# MCU.net
KiCad netlist of a schematic drawn in Altium Designer
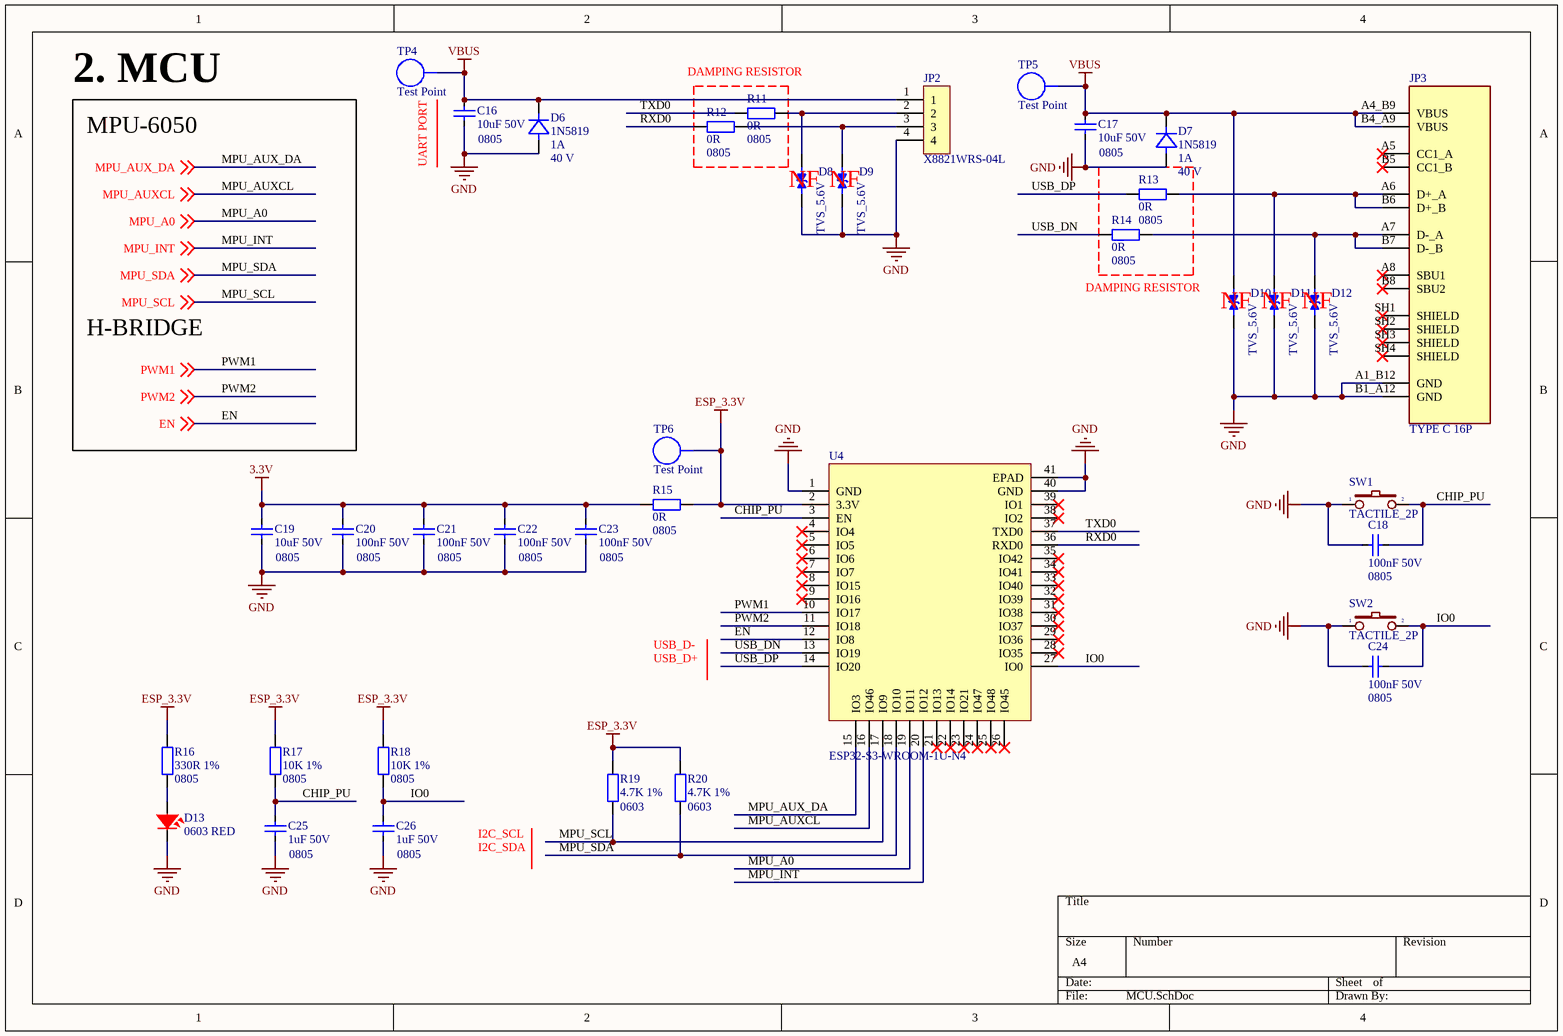
[diagram p0: MCU.SchDoc]

(export (version "E")
  (design (tool "Eeschema 10.0.6"))
  (components
    (comp (ref "C16")
      (value "10uF 50V")
      (footprint "CAP_SMD_0805_NEW")
      (description "10 µF ±20% 50V Ceramic Capacitor X5R 0805 (2012 Metric)")
      (fields
        (field (name "MANUFACTURER") "Murata Electronics")
        (field (name "MANUFACTURE PART NUMBER") "GRM21BR61H106ME43L")
        (field (name "SIZE") "0805")
      )
      (libsource (lib "Capacitors") (part "C0805_MLCC_10uF_50V"))
    )
    (comp (ref "C17")
      (value "10uF 50V")
      (footprint "CAP_SMD_0805_NEW")
      (description "10 µF ±20% 50V Ceramic Capacitor X5R 0805 (2012 Metric)")
      (fields
        (field (name "MANUFACTURER") "Murata Electronics")
        (field (name "MANUFACTURE PART NUMBER") "GRM21BR61H106ME43L")
        (field (name "SIZE") "0805")
      )
      (libsource (lib "Capacitors") (part "C0805_MLCC_10uF_50V"))
    )
    (comp (ref "C18")
      (value "100nF 50V")
      (footprint "CAP_SMD_0805_NEW")
      (description "0.1 µF ±10% 50V Ceramic Capacitor X7R 0805 (2012 Metric)")
      (fields
        (field (name "MANUFACTURER") "YAGEO")
        (field (name "MANUFACTURE PART NUMBER") "CC0805KRX7R9BB104")
        (field (name "SIZE") "0805")
      )
      (libsource (lib "Capacitors") (part "C0805_MLCC_100nF_50V"))
    )
    (comp (ref "C19")
      (value "10uF 50V")
      (footprint "CAP_SMD_0805_NEW")
      (description "10 µF ±20% 50V Ceramic Capacitor X5R 0805 (2012 Metric)")
      (fields
        (field (name "MANUFACTURER") "Murata Electronics")
        (field (name "MANUFACTURE PART NUMBER") "GRM21BR61H106ME43L")
        (field (name "SIZE") "0805")
      )
      (libsource (lib "Capacitors") (part "C0805_MLCC_10uF_50V"))
    )
    (comp (ref "C20")
      (value "100nF 50V")
      (footprint "CAP_SMD_0805_NEW")
      (description "0.1 µF ±10% 50V Ceramic Capacitor X7R 0805 (2012 Metric)")
      (fields
        (field (name "MANUFACTURER") "YAGEO")
        (field (name "MANUFACTURE PART NUMBER") "CC0805KRX7R9BB104")
        (field (name "SIZE") "0805")
      )
      (libsource (lib "Capacitors") (part "C0805_MLCC_100nF_50V"))
    )
    (comp (ref "C21")
      (value "100nF 50V")
      (footprint "CAP_SMD_0805_NEW")
      (description "0.1 µF ±10% 50V Ceramic Capacitor X7R 0805 (2012 Metric)")
      (fields
        (field (name "MANUFACTURER") "YAGEO")
        (field (name "MANUFACTURE PART NUMBER") "CC0805KRX7R9BB104")
        (field (name "SIZE") "0805")
      )
      (libsource (lib "Capacitors") (part "C0805_MLCC_100nF_50V"))
    )
    (comp (ref "C22")
      (value "100nF 50V")
      (footprint "CAP_SMD_0805_NEW")
      (description "0.1 µF ±10% 50V Ceramic Capacitor X7R 0805 (2012 Metric)")
      (fields
        (field (name "MANUFACTURER") "YAGEO")
        (field (name "MANUFACTURE PART NUMBER") "CC0805KRX7R9BB104")
        (field (name "SIZE") "0805")
      )
      (libsource (lib "Capacitors") (part "C0805_MLCC_100nF_50V"))
    )
    (comp (ref "C23")
      (value "100nF 50V")
      (footprint "CAP_SMD_0805_NEW")
      (description "0.1 µF ±10% 50V Ceramic Capacitor X7R 0805 (2012 Metric)")
      (fields
        (field (name "MANUFACTURER") "YAGEO")
        (field (name "MANUFACTURE PART NUMBER") "CC0805KRX7R9BB104")
        (field (name "SIZE") "0805")
      )
      (libsource (lib "Capacitors") (part "C0805_MLCC_100nF_50V"))
    )
    (comp (ref "C24")
      (value "100nF 50V")
      (footprint "CAP_SMD_0805_NEW")
      (description "0.1 µF ±10% 50V Ceramic Capacitor X7R 0805 (2012 Metric)")
      (fields
        (field (name "MANUFACTURER") "YAGEO")
        (field (name "MANUFACTURE PART NUMBER") "CC0805KRX7R9BB104")
        (field (name "SIZE") "0805")
      )
      (libsource (lib "Capacitors") (part "C0805_MLCC_100nF_50V"))
    )
    (comp (ref "C25")
      (value "1uF 50V")
      (footprint "CAP_SMD_0805_NEW")
      (description "1 µF ±10% 50V Ceramic Capacitor X7R 0805 (2012 Metric)")
      (fields
        (field (name "MANUFACTURER") "Samsung Electro-Mechanics")
        (field (name "MANUFACTURE PART NUMBER") "CL21B105KBFNNNG")
        (field (name "SIZE") "0805")
      )
      (libsource (lib "Capacitors") (part "C0805_MLCC_1uF_50V"))
    )
    (comp (ref "C26")
      (value "1uF 50V")
      (footprint "CAP_SMD_0805_NEW")
      (description "1 µF ±10% 50V Ceramic Capacitor X7R 0805 (2012 Metric)")
      (fields
        (field (name "MANUFACTURER") "Samsung Electro-Mechanics")
        (field (name "MANUFACTURE PART NUMBER") "CL21B105KBFNNNG")
        (field (name "SIZE") "0805")
      )
      (libsource (lib "Capacitors") (part "C0805_MLCC_1uF_50V"))
    )
    (comp (ref "D6")
      (value "1N5819")
      (footprint "DIO-SMD-123")
      (description "Diode 40 V 1A Surface Mount SOD-123")
      (fields
        (field (name "MANUFACTURER") "Diodes Incorporated")
        (field (name "MANUFACTURE PART NUMBER") "1N5819HW-7-F")
        (field (name "CURRENT - AVERAGE RECTIFIED (IO)") "1A")
        (field (name "VOLTAGE - DC REVERSE (VR) (MAX)") "40 V")
      )
      (libsource (lib "Diode") (part "1N5819"))
    )
    (comp (ref "D7")
      (value "1N5819")
      (footprint "DIO-SMD-123")
      (description "Diode 40 V 1A Surface Mount SOD-123")
      (fields
        (field (name "MANUFACTURER") "Diodes Incorporated")
        (field (name "MANUFACTURE PART NUMBER") "1N5819HW-7-F")
        (field (name "CURRENT - AVERAGE RECTIFIED (IO)") "1A")
        (field (name "VOLTAGE - DC REVERSE (VR) (MAX)") "40 V")
      )
      (libsource (lib "Diode") (part "1N5819"))
    )
    (comp (ref "D8")
      (value "TVS_5.6V")
      (footprint "SOD_523")
      (description "9.4A 18.6V 5.6V Bi-Directional 5V SOD-523 Electrostatic and Surge Protection (TVS/ESD) ROHS")
      (fields (field (name "MANUFACTURER") "LRC") (field (name "MANUFACTURE PART NUMBER") "LESD5D5.0CT1G"))
      (libsource (lib "Diode") (part "TVS_5.6V"))
    )
    (comp (ref "D9")
      (value "TVS_5.6V")
      (footprint "SOD_523")
      (description "9.4A 18.6V 5.6V Bi-Directional 5V SOD-523 Electrostatic and Surge Protection (TVS/ESD) ROHS")
      (fields (field (name "MANUFACTURER") "LRC") (field (name "MANUFACTURE PART NUMBER") "LESD5D5.0CT1G"))
      (libsource (lib "Diode") (part "TVS_5.6V"))
    )
    (comp (ref "D10")
      (value "TVS_5.6V")
      (footprint "SOD_523")
      (description "9.4A 18.6V 5.6V Bi-Directional 5V SOD-523 Electrostatic and Surge Protection (TVS/ESD) ROHS")
      (fields (field (name "MANUFACTURER") "LRC") (field (name "MANUFACTURE PART NUMBER") "LESD5D5.0CT1G"))
      (libsource (lib "Diode") (part "TVS_5.6V"))
    )
    (comp (ref "D11")
      (value "TVS_5.6V")
      (footprint "SOD_523")
      (description "9.4A 18.6V 5.6V Bi-Directional 5V SOD-523 Electrostatic and Surge Protection (TVS/ESD) ROHS")
      (fields (field (name "MANUFACTURER") "LRC") (field (name "MANUFACTURE PART NUMBER") "LESD5D5.0CT1G"))
      (libsource (lib "Diode") (part "TVS_5.6V"))
    )
    (comp (ref "D12")
      (value "TVS_5.6V")
      (footprint "SOD_523")
      (description "9.4A 18.6V 5.6V Bi-Directional 5V SOD-523 Electrostatic and Surge Protection (TVS/ESD) ROHS")
      (fields (field (name "MANUFACTURER") "LRC") (field (name "MANUFACTURE PART NUMBER") "LESD5D5.0CT1G"))
      (libsource (lib "Diode") (part "TVS_5.6V"))
    )
    (comp (ref "D13")
      (value "0603 RED")
      (footprint "LED-0603")
      (description "Red 625nm LED Indication - Discrete 2V 0603 (1608 Metric)")
      (fields
        (field (name "MANUFACTURER") "Würth Elektronik")
        (field (name "MANUFACTURE PART NUMBER") "150060RS75000")
      )
      (libsource (lib "LEDs") (part "LED_0603_RED"))
    )
    (comp (ref "JP2")
      (value "X8821WRS-04L")
      (footprint "CONN_X8821WRS-04L-LPSN")
      (fields
        (field (name "MANUFACTURER") "XKB Connection")
        (field (name "MANUFACTURE PART NUMBER") "X8821WRS-04-9TSN")
      )
      (libsource (lib "Connectors") (part "X8821WRS-04L"))
    )
    (comp (ref "JP3")
      (value "TYPE C 16P")
      (footprint "TYPE C 16P")
      (fields
        (field (name "MANUFACTURER") "Amphenol ICC (Commercial Products)")
        (field (name "MANUFACTURE PART NUMBER") "12402012E212A")
      )
      (libsource (lib "Connectors") (part "TYPE_C_16P"))
    )
    (comp (ref "R11")
      (value "0R")
      (footprint "RES_SMD_0805")
      (description "0 Ohms Jumper Chip Resistor 0805 (2012 Metric) Automotive AEC-Q200 Thick Film")
      (fields
        (field (name "MANUFACTURER") "Vishay Dale")
        (field (name "MANUFACTURE PART NUMBER") "CRCW08050000Z0EA")
        (field (name "SIZE") "0805")
      )
      (libsource (lib "Resistors") (part "R0805_0R"))
    )
    (comp (ref "R12")
      (value "0R")
      (footprint "RES_SMD_0805")
      (description "0 Ohms Jumper Chip Resistor 0805 (2012 Metric) Automotive AEC-Q200 Thick Film")
      (fields
        (field (name "MANUFACTURER") "Vishay Dale")
        (field (name "MANUFACTURE PART NUMBER") "CRCW08050000Z0EA")
        (field (name "SIZE") "0805")
      )
      (libsource (lib "Resistors") (part "R0805_0R"))
    )
    (comp (ref "R13")
      (value "0R")
      (footprint "RES_SMD_0805")
      (description "0 Ohms Jumper Chip Resistor 0805 (2012 Metric) Automotive AEC-Q200 Thick Film")
      (fields
        (field (name "MANUFACTURER") "Vishay Dale")
        (field (name "MANUFACTURE PART NUMBER") "CRCW08050000Z0EA")
        (field (name "SIZE") "0805")
      )
      (libsource (lib "Resistors") (part "R0805_0R"))
    )
    (comp (ref "R14")
      (value "0R")
      (footprint "RES_SMD_0805")
      (description "0 Ohms Jumper Chip Resistor 0805 (2012 Metric) Automotive AEC-Q200 Thick Film")
      (fields
        (field (name "MANUFACTURER") "Vishay Dale")
        (field (name "MANUFACTURE PART NUMBER") "CRCW08050000Z0EA")
        (field (name "SIZE") "0805")
      )
      (libsource (lib "Resistors") (part "R0805_0R"))
    )
    (comp (ref "R15")
      (value "0R")
      (footprint "RES_SMD_0805")
      (description "0 Ohms Jumper Chip Resistor 0805 (2012 Metric) Automotive AEC-Q200 Thick Film")
      (fields
        (field (name "MANUFACTURER") "Vishay Dale")
        (field (name "MANUFACTURE PART NUMBER") "CRCW08050000Z0EA")
        (field (name "SIZE") "0805")
      )
      (libsource (lib "Resistors") (part "R0805_0R"))
    )
    (comp (ref "R16")
      (value "330R 1%")
      (footprint "RES_SMD_0805")
      (description "330 Ohms ±1% 0.125W, 1/8W Chip Resistor 0805 (2012 Metric) Automotive AEC-Q200 Thick Film")
      (fields
        (field (name "MANUFACTURER") "Stackpole Electronics Inc")
        (field (name "MANUFACTURE PART NUMBER") "RMCF0805FT330R")
        (field (name "SIZE") "0805")
      )
      (libsource (lib "Resistors") (part "R0805_330R"))
    )
    (comp (ref "R17")
      (value "10K 1%")
      (footprint "RES_SMD_0805")
      (description "10 kOhms ±1% 0.125W, 1/8W Chip Resistor 0805 (2012 Metric) Moisture Resistant Thick Film")
      (fields
        (field (name "MANUFACTURER") "YAGEO")
        (field (name "MANUFACTURE PART NUMBER") "RC0805FR-0710KL")
        (field (name "SIZE") "0805")
      )
      (libsource (lib "Resistors") (part "R0805_10K"))
    )
    (comp (ref "R18")
      (value "10K 1%")
      (footprint "RES_SMD_0805")
      (description "10 kOhms ±1% 0.125W, 1/8W Chip Resistor 0805 (2012 Metric) Moisture Resistant Thick Film")
      (fields
        (field (name "MANUFACTURER") "YAGEO")
        (field (name "MANUFACTURE PART NUMBER") "RC0805FR-0710KL")
        (field (name "SIZE") "0805")
      )
      (libsource (lib "Resistors") (part "R0805_10K"))
    )
    (comp (ref "R19")
      (value "4.7K 1%")
      (footprint "RES_SMD_0603")
      (description "4.7 kOhms ±1% 0.1W, 1/10W Chip Resistor 0603 (1608 Metric) Moisture Resistant Thick Film")
      (fields
        (field (name "MANUFACTURER") "YAGEO")
        (field (name "MANUFACTURE PART NUMBER") "RC0603FR-074K7L")
        (field (name "SIZE") "0603")
      )
      (libsource (lib "Resistors") (part "R0603_4.7K"))
    )
    (comp (ref "R20")
      (value "4.7K 1%")
      (footprint "RES_SMD_0603")
      (description "4.7 kOhms ±1% 0.1W, 1/10W Chip Resistor 0603 (1608 Metric) Moisture Resistant Thick Film")
      (fields
        (field (name "MANUFACTURER") "YAGEO")
        (field (name "MANUFACTURE PART NUMBER") "RC0603FR-074K7L")
        (field (name "SIZE") "0603")
      )
      (libsource (lib "Resistors") (part "R0603_4.7K"))
    )
    (comp (ref "SW1")
      (value "TACTILE_2P")
      (footprint "C&K SW 2P")
      (description "Tactile Switch SPST-NO Top Actuated Surface Mount")
      (fields
        (field (name "MANUFACTURER") "C&K")
        (field (name "MANUFACTURE PART NUMBER") "PTS636 SM25F SMTR LFS")
      )
      (libsource (lib "Button") (part "SWITCH_TACTILE_SPST"))
    )
    (comp (ref "SW2")
      (value "TACTILE_2P")
      (footprint "C&K SW 2P")
      (description "Tactile Switch SPST-NO Top Actuated Surface Mount")
      (fields
        (field (name "MANUFACTURER") "C&K")
        (field (name "MANUFACTURE PART NUMBER") "PTS636 SM25F SMTR LFS")
      )
      (libsource (lib "Button") (part "SWITCH_TACTILE_SPST"))
    )
    (comp (ref "TP4")
      (value "Test Point")
      (footprint "TEST_POINT")
      (libsource (lib "Connectors") (part "TEST_POINT"))
    )
    (comp (ref "TP5")
      (value "Test Point")
      (footprint "TEST_POINT")
      (libsource (lib "Connectors") (part "TEST_POINT"))
    )
    (comp (ref "TP6")
      (value "Test Point")
      (footprint "TEST_POINT")
      (libsource (lib "Connectors") (part "TEST_POINT"))
    )
    (comp (ref "U4")
      (value "ESP32-S3-WROOM-1U-N4")
      (footprint "ESP32-S3-WROOM-1U")
      (description "SMD,18x19.2mm WiFi Modules ROHS")
      (fields (field (name "MANUFACTURER") "Espressif Systems"))
      (libsource (lib "MCU") (part "ESP32-S3-WROOM-1U-N4"))
    )
  )
  (nets
    (net (code "1") (name "/CHIP_PU") (class "Default")
      (node (ref "C18") (pin "1") (pinfunction "1_1") (pintype "passive"))
      (node (ref "C25") (pin "2") (pinfunction "2_2") (pintype "passive"))
      (node (ref "R17") (pin "1") (pinfunction "1_1") (pintype "passive"))
      (node (ref "SW1") (pin "2") (pinfunction "2_2") (pintype "passive"))
      (node (ref "U4") (pin "3") (pinfunction "EN_3") (pintype "passive"))
    )
    (net (code "2") (name "/IO0") (class "Default")
      (node (ref "C24") (pin "1") (pinfunction "1_1") (pintype "passive"))
      (node (ref "C26") (pin "2") (pinfunction "2_2") (pintype "passive"))
      (node (ref "R18") (pin "1") (pinfunction "1_1") (pintype "passive"))
      (node (ref "SW2") (pin "2") (pinfunction "2_2") (pintype "passive"))
      (node (ref "U4") (pin "27") (pinfunction "IO0_27") (pintype "passive"))
    )
    (net (code "3") (name "/RXD0") (class "Default")
      (node (ref "R12") (pin "2") (pinfunction "2_2") (pintype "passive"))
      (node (ref "U4") (pin "36") (pinfunction "RXD0_36") (pintype "passive"))
    )
    (net (code "4") (name "/TXD0") (class "Default")
      (node (ref "R11") (pin "2") (pinfunction "2_2") (pintype "passive"))
      (node (ref "U4") (pin "37") (pinfunction "TXD0_37") (pintype "passive"))
    )
    (net (code "5") (name "/USB_DN") (class "Default")
      (node (ref "R14") (pin "2") (pinfunction "2_2") (pintype "passive"))
      (node (ref "U4") (pin "13") (pinfunction "IO19_13") (pintype "passive"))
    )
    (net (code "6") (name "/USB_DP") (class "Default")
      (node (ref "R13") (pin "2") (pinfunction "2_2") (pintype "passive"))
      (node (ref "U4") (pin "14") (pinfunction "IO20_14") (pintype "passive"))
    )
    (net (code "7") (name "3.3V") (class "Default")
      (node (ref "C19") (pin "2") (pinfunction "2_2") (pintype "passive"))
      (node (ref "C20") (pin "2") (pinfunction "2_2") (pintype "passive"))
      (node (ref "C21") (pin "2") (pinfunction "2_2") (pintype "passive"))
      (node (ref "C22") (pin "2") (pinfunction "2_2") (pintype "passive"))
      (node (ref "C23") (pin "2") (pinfunction "2_2") (pintype "passive"))
      (node (ref "R15") (pin "2") (pinfunction "2_2") (pintype "passive"))
    )
    (net (code "8") (name "EN") (class "Default")
      (node (ref "U4") (pin "12") (pinfunction "IO8_12") (pintype "passive"))
    )
    (net (code "9") (name "ESP_3.3V") (class "Default")
      (node (ref "R15") (pin "1") (pinfunction "1_1") (pintype "passive"))
      (node (ref "R16") (pin "2") (pinfunction "2_2") (pintype "passive"))
      (node (ref "R17") (pin "2") (pinfunction "2_2") (pintype "passive"))
      (node (ref "R18") (pin "2") (pinfunction "2_2") (pintype "passive"))
      (node (ref "R19") (pin "2") (pinfunction "2_2") (pintype "passive"))
      (node (ref "R20") (pin "2") (pinfunction "2_2") (pintype "passive"))
      (node (ref "TP6") (pin "1") (pinfunction "1_1") (pintype "passive"))
      (node (ref "U4") (pin "2") (pinfunction "3.3V_2") (pintype "passive"))
    )
    (net (code "10") (name "GND") (class "Default")
      (node (ref "C16") (pin "1") (pinfunction "1_1") (pintype "passive"))
      (node (ref "C17") (pin "1") (pinfunction "1_1") (pintype "passive"))
      (node (ref "C18") (pin "2") (pinfunction "2_2") (pintype "passive"))
      (node (ref "C19") (pin "1") (pinfunction "1_1") (pintype "passive"))
      (node (ref "C20") (pin "1") (pinfunction "1_1") (pintype "passive"))
      (node (ref "C21") (pin "1") (pinfunction "1_1") (pintype "passive"))
      (node (ref "C22") (pin "1") (pinfunction "1_1") (pintype "passive"))
      (node (ref "C23") (pin "1") (pinfunction "1_1") (pintype "passive"))
      (node (ref "C24") (pin "2") (pinfunction "2_2") (pintype "passive"))
      (node (ref "C25") (pin "1") (pinfunction "1_1") (pintype "passive"))
      (node (ref "C26") (pin "1") (pinfunction "1_1") (pintype "passive"))
      (node (ref "D10") (pin "1") (pinfunction "1_1") (pintype "passive"))
      (node (ref "D11") (pin "1") (pinfunction "1_1") (pintype "passive"))
      (node (ref "D12") (pin "1") (pinfunction "1_1") (pintype "passive"))
      (node (ref "D13") (pin "2") (pinfunction "2_2") (pintype "passive"))
      (node (ref "D6") (pin "A") (pinfunction "A_A") (pintype "passive"))
      (node (ref "D7") (pin "A") (pinfunction "A_A") (pintype "passive"))
      (node (ref "D8") (pin "1") (pinfunction "1_1") (pintype "passive"))
      (node (ref "D9") (pin "1") (pinfunction "1_1") (pintype "passive"))
      (node (ref "JP2") (pin "4") (pinfunction "4_4") (pintype "passive"))
      (node (ref "JP3") (pin "A1_B12") (pinfunction "GND_A1_B12") (pintype "passive"))
      (node (ref "JP3") (pin "B1_A12") (pinfunction "GND_B1_A12") (pintype "passive"))
      (node (ref "SW1") (pin "1") (pinfunction "1_1") (pintype "passive"))
      (node (ref "SW2") (pin "1") (pinfunction "1_1") (pintype "passive"))
      (node (ref "U4") (pin "1") (pinfunction "GND_1") (pintype "passive"))
      (node (ref "U4") (pin "40") (pinfunction "GND_40") (pintype "passive"))
      (node (ref "U4") (pin "41") (pinfunction "EPAD_41") (pintype "passive"))
    )
    (net (code "11") (name "MPU_A0") (class "Default")
      (node (ref "U4") (pin "19") (pinfunction "IO11_19") (pintype "passive"))
    )
    (net (code "12") (name "MPU_AUXCL") (class "Default")
      (node (ref "U4") (pin "16") (pinfunction "IO46_16") (pintype "passive"))
    )
    (net (code "13") (name "MPU_AUX_DA") (class "Default")
      (node (ref "U4") (pin "15") (pinfunction "IO3_15") (pintype "passive"))
    )
    (net (code "14") (name "MPU_INT") (class "Default")
      (node (ref "U4") (pin "20") (pinfunction "IO12_20") (pintype "passive"))
    )
    (net (code "15") (name "MPU_SCL") (class "Default")
      (node (ref "R19") (pin "1") (pinfunction "1_1") (pintype "passive"))
      (node (ref "U4") (pin "17") (pinfunction "IO9_17") (pintype "passive"))
    )
    (net (code "16") (name "MPU_SDA") (class "Default")
      (node (ref "R20") (pin "1") (pinfunction "1_1") (pintype "passive"))
      (node (ref "U4") (pin "18") (pinfunction "IO10_18") (pintype "passive"))
    )
    (net (code "17") (name "Net-(D8-Pad2)") (class "Default")
      (node (ref "D8") (pin "2") (pinfunction "2_2") (pintype "passive"))
      (node (ref "JP2") (pin "2") (pinfunction "2_2") (pintype "passive"))
      (node (ref "R11") (pin "1") (pinfunction "1_1") (pintype "passive"))
    )
    (net (code "18") (name "Net-(D9-Pad2)") (class "Default")
      (node (ref "D9") (pin "2") (pinfunction "2_2") (pintype "passive"))
      (node (ref "JP2") (pin "3") (pinfunction "3_3") (pintype "passive"))
      (node (ref "R12") (pin "1") (pinfunction "1_1") (pintype "passive"))
    )
    (net (code "19") (name "Net-(D13-Pad1)") (class "Default")
      (node (ref "D13") (pin "1") (pinfunction "1_1") (pintype "passive"))
      (node (ref "R16") (pin "1") (pinfunction "1_1") (pintype "passive"))
    )
    (net (code "20") (name "Net-(JP3-D+_A)") (class "Default")
      (node (ref "D11") (pin "2") (pinfunction "2_2") (pintype "passive"))
      (node (ref "JP3") (pin "A6") (pinfunction "D+_A_A6") (pintype "passive"))
      (node (ref "JP3") (pin "B6") (pinfunction "D+_B_B6") (pintype "passive"))
      (node (ref "R13") (pin "1") (pinfunction "1_1") (pintype "passive"))
    )
    (net (code "21") (name "Net-(JP3-D-_A)") (class "Default")
      (node (ref "D12") (pin "2") (pinfunction "2_2") (pintype "passive"))
      (node (ref "JP3") (pin "A7") (pinfunction "D-_A_A7") (pintype "passive"))
      (node (ref "JP3") (pin "B7") (pinfunction "D-_B_B7") (pintype "passive"))
      (node (ref "R14") (pin "1") (pinfunction "1_1") (pintype "passive"))
    )
    (net (code "22") (name "PWM1") (class "Default")
      (node (ref "U4") (pin "10") (pinfunction "IO17_10") (pintype "passive"))
    )
    (net (code "23") (name "PWM2") (class "Default")
      (node (ref "U4") (pin "11") (pinfunction "IO18_11") (pintype "passive"))
    )
    (net (code "24") (name "VBUS") (class "Default")
      (node (ref "C16") (pin "2") (pinfunction "2_2") (pintype "passive"))
      (node (ref "C17") (pin "2") (pinfunction "2_2") (pintype "passive"))
      (node (ref "D10") (pin "2") (pinfunction "2_2") (pintype "passive"))
      (node (ref "D6") (pin "C") (pinfunction "C_C") (pintype "passive"))
      (node (ref "D7") (pin "C") (pinfunction "C_C") (pintype "passive"))
      (node (ref "JP2") (pin "1") (pinfunction "1_1") (pintype "passive"))
      (node (ref "JP3") (pin "A4_B9") (pinfunction "VBUS_A4_B9") (pintype "passive"))
      (node (ref "JP3") (pin "B4_A9") (pinfunction "VBUS_B4_A9") (pintype "passive"))
      (node (ref "TP4") (pin "1") (pinfunction "1_1") (pintype "passive"))
      (node (ref "TP5") (pin "1") (pinfunction "1_1") (pintype "passive"))
    )
    (net (code "25") (name "unconnected-(JP3-CC1_A-PadA5)") (class "Default")
      (node (ref "JP3") (pin "A5") (pinfunction "CC1_A_A5") (pintype "passive+no_connect"))
    )
    (net (code "26") (name "unconnected-(JP3-CC1_B-PadB5)") (class "Default")
      (node (ref "JP3") (pin "B5") (pinfunction "CC1_B_B5") (pintype "passive+no_connect"))
    )
    (net (code "27") (name "unconnected-(JP3-SBU1-PadA8)") (class "Default")
      (node (ref "JP3") (pin "A8") (pinfunction "SBU1_A8") (pintype "passive+no_connect"))
    )
    (net (code "28") (name "unconnected-(JP3-SBU2-PadB8)") (class "Default")
      (node (ref "JP3") (pin "B8") (pinfunction "SBU2_B8") (pintype "passive+no_connect"))
    )
    (net (code "29") (name "unconnected-(JP3-SHIELD-PadSH1)") (class "Default")
      (node (ref "JP3") (pin "SH1") (pinfunction "SHIELD_SH1") (pintype "passive+no_connect"))
    )
    (net (code "30") (name "unconnected-(JP3-SHIELD-PadSH2)") (class "Default")
      (node (ref "JP3") (pin "SH2") (pinfunction "SHIELD_SH2") (pintype "passive+no_connect"))
    )
    (net (code "31") (name "unconnected-(JP3-SHIELD-PadSH3)") (class "Default")
      (node (ref "JP3") (pin "SH3") (pinfunction "SHIELD_SH3") (pintype "passive+no_connect"))
    )
    (net (code "32") (name "unconnected-(JP3-SHIELD-PadSH4)") (class "Default")
      (node (ref "JP3") (pin "SH4") (pinfunction "SHIELD_SH4") (pintype "passive+no_connect"))
    )
    (net (code "33") (name "unconnected-(U4-IO1-Pad39)") (class "Default")
      (node (ref "U4") (pin "39") (pinfunction "IO1_39") (pintype "passive+no_connect"))
    )
    (net (code "34") (name "unconnected-(U4-IO2-Pad38)") (class "Default")
      (node (ref "U4") (pin "38") (pinfunction "IO2_38") (pintype "passive+no_connect"))
    )
    (net (code "35") (name "unconnected-(U4-IO4-Pad4)") (class "Default")
      (node (ref "U4") (pin "4") (pinfunction "IO4_4") (pintype "passive+no_connect"))
    )
    (net (code "36") (name "unconnected-(U4-IO5-Pad5)") (class "Default")
      (node (ref "U4") (pin "5") (pinfunction "IO5_5") (pintype "passive+no_connect"))
    )
    (net (code "37") (name "unconnected-(U4-IO6-Pad6)") (class "Default")
      (node (ref "U4") (pin "6") (pinfunction "IO6_6") (pintype "passive+no_connect"))
    )
    (net (code "38") (name "unconnected-(U4-IO7-Pad7)") (class "Default")
      (node (ref "U4") (pin "7") (pinfunction "IO7_7") (pintype "passive+no_connect"))
    )
    (net (code "39") (name "unconnected-(U4-IO13-Pad21)") (class "Default")
      (node (ref "U4") (pin "21") (pinfunction "IO13_21") (pintype "passive+no_connect"))
    )
    (net (code "40") (name "unconnected-(U4-IO14-Pad22)") (class "Default")
      (node (ref "U4") (pin "22") (pinfunction "IO14_22") (pintype "passive+no_connect"))
    )
    (net (code "41") (name "unconnected-(U4-IO15-Pad8)") (class "Default")
      (node (ref "U4") (pin "8") (pinfunction "IO15_8") (pintype "passive+no_connect"))
    )
    (net (code "42") (name "unconnected-(U4-IO16-Pad9)") (class "Default")
      (node (ref "U4") (pin "9") (pinfunction "IO16_9") (pintype "passive+no_connect"))
    )
    (net (code "43") (name "unconnected-(U4-IO21-Pad23)") (class "Default")
      (node (ref "U4") (pin "23") (pinfunction "IO21_23") (pintype "passive+no_connect"))
    )
    (net (code "44") (name "unconnected-(U4-IO35-Pad28)") (class "Default")
      (node (ref "U4") (pin "28") (pinfunction "IO35_28") (pintype "passive+no_connect"))
    )
    (net (code "45") (name "unconnected-(U4-IO36-Pad29)") (class "Default")
      (node (ref "U4") (pin "29") (pinfunction "IO36_29") (pintype "passive+no_connect"))
    )
    (net (code "46") (name "unconnected-(U4-IO37-Pad30)") (class "Default")
      (node (ref "U4") (pin "30") (pinfunction "IO37_30") (pintype "passive+no_connect"))
    )
    (net (code "47") (name "unconnected-(U4-IO38-Pad31)") (class "Default")
      (node (ref "U4") (pin "31") (pinfunction "IO38_31") (pintype "passive+no_connect"))
    )
    (net (code "48") (name "unconnected-(U4-IO39-Pad32)") (class "Default")
      (node (ref "U4") (pin "32") (pinfunction "IO39_32") (pintype "passive+no_connect"))
    )
    (net (code "49") (name "unconnected-(U4-IO40-Pad33)") (class "Default")
      (node (ref "U4") (pin "33") (pinfunction "IO40_33") (pintype "passive+no_connect"))
    )
    (net (code "50") (name "unconnected-(U4-IO41-Pad34)") (class "Default")
      (node (ref "U4") (pin "34") (pinfunction "IO41_34") (pintype "passive+no_connect"))
    )
    (net (code "51") (name "unconnected-(U4-IO42-Pad35)") (class "Default")
      (node (ref "U4") (pin "35") (pinfunction "IO42_35") (pintype "passive+no_connect"))
    )
    (net (code "52") (name "unconnected-(U4-IO45-Pad26)") (class "Default")
      (node (ref "U4") (pin "26") (pinfunction "IO45_26") (pintype "passive+no_connect"))
    )
    (net (code "53") (name "unconnected-(U4-IO47-Pad24)") (class "Default")
      (node (ref "U4") (pin "24") (pinfunction "IO47_24") (pintype "passive+no_connect"))
    )
    (net (code "54") (name "unconnected-(U4-IO48-Pad25)") (class "Default")
      (node (ref "U4") (pin "25") (pinfunction "IO48_25") (pintype "passive+no_connect"))
    )
  )
)
